# snow_depth_gauge_2A.net
KiCad netlist of a schematic drawn in EAGLE
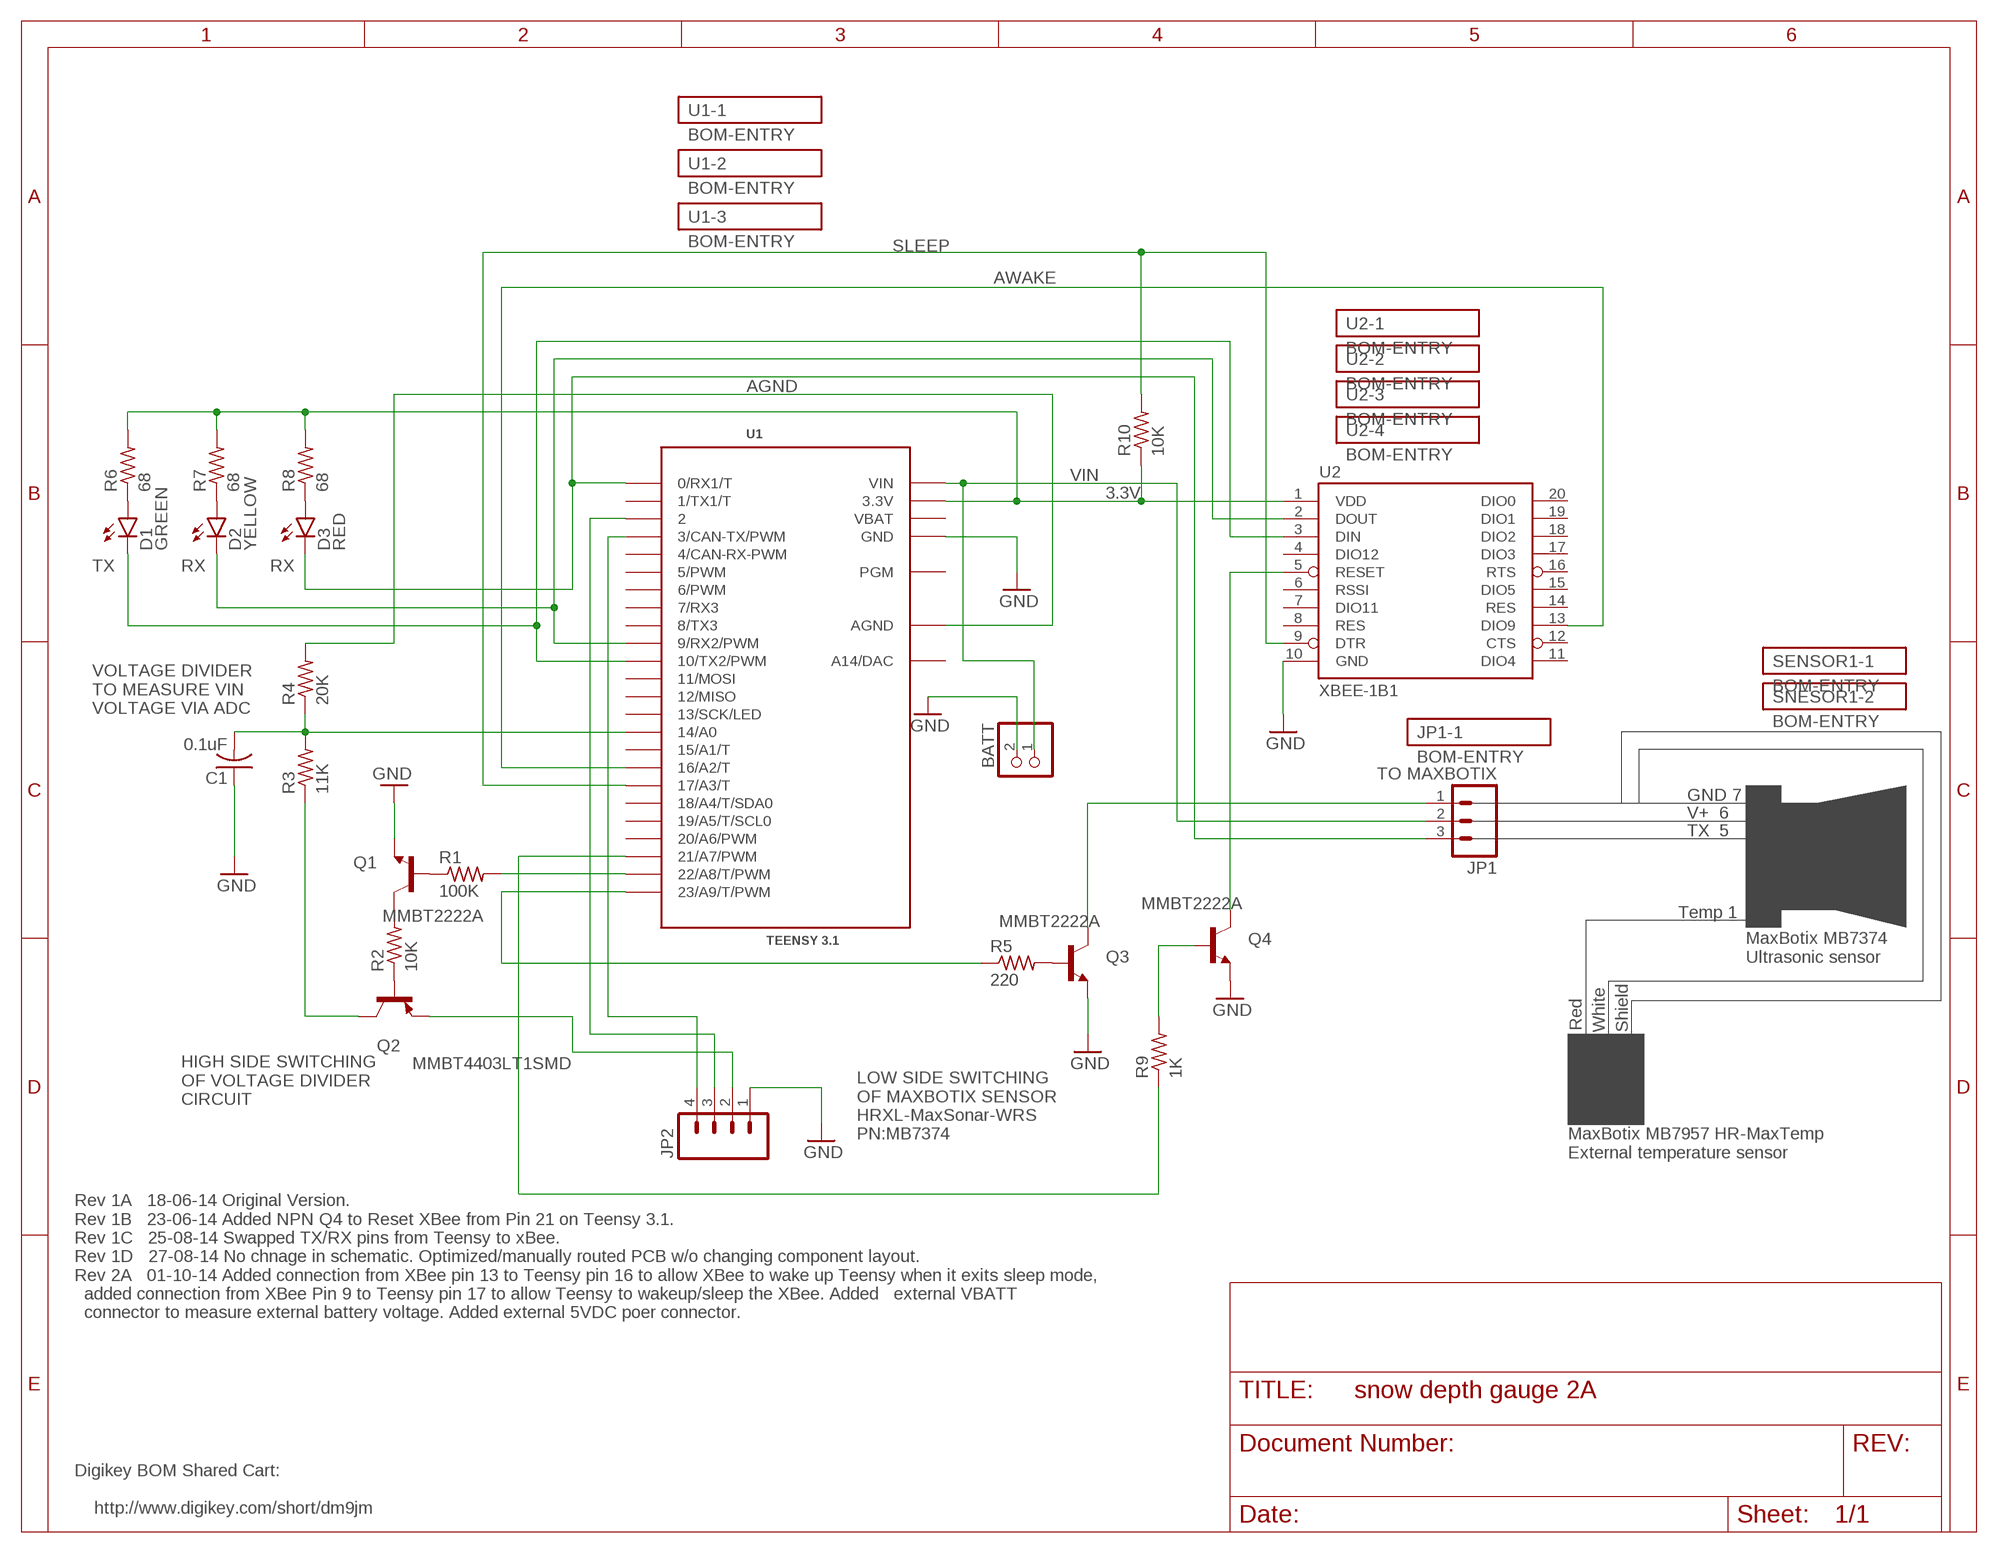
[diagram p0: schematic, sheet 1]

(export (version "E")
  (design (tool "Eeschema 10.0.6"))
  (components
    (comp (ref "BATT")
      (value "JST_2PIN-SMT-RA")
      (footprint "eagle-import:JST-PH-2-SMT-RA")
      (libsource (lib "eagle-import") (part "JST_2PIN-SMT-RA"))
    )
    (comp (ref "C1")
      (value "0.1uF")
      (footprint "eagle-import:C3216")
      (fields (field (name "PARTNO") "C1206C104K4RACTU"))
      (libsource (lib "eagle-import") (part "C-USC3216"))
    )
    (comp (ref "D1")
      (value "GREEN")
      (footprint "eagle-import:LED-0603")
      (fields (field (name "PARTNO") "LNJ337W83RA"))
      (libsource (lib "eagle-import") (part "LED-GREEN0603"))
    )
    (comp (ref "D2")
      (value "YELLOW")
      (footprint "eagle-import:LED-0603")
      (fields (field (name "PARTNO") "LNJ437W84RA"))
      (libsource (lib "eagle-import") (part "LED-YELLOW0603"))
    )
    (comp (ref "D3")
      (value "RED")
      (footprint "eagle-import:LED-0603")
      (fields (field (name "PARTNO") "LNJ237W82RA"))
      (libsource (lib "eagle-import") (part "LED-RED0603"))
    )
    (comp (ref "JP1")
      (value "TO MAXBOTIX")
      (footprint "eagle-import:MOLEX-1X3_LOCK")
      (fields (field (name "PARTNO") "0022292031"))
      (libsource (lib "eagle-import") (part "M03POLAR_LOCK"))
    )
    (comp (ref "JP2")
      (value "M04PTH")
      (footprint "eagle-import:1X04")
      (libsource (lib "eagle-import") (part "M04PTH"))
    )
    (comp (ref "Q1")
      (value "MMBT2222A")
      (footprint "eagle-import:SOT23-BEC")
      (libsource (lib "eagle-import") (part "-NPN-SOT23-BECMMBT2222ALT1"))
    )
    (comp (ref "Q2")
      (value "MMBT4403LT1SMD")
      (footprint "eagle-import:SOT23-BEC")
      (fields (field (name "PARTNO") "MMBT4403"))
      (libsource (lib "eagle-import") (part "MMBT4403SMDLT1"))
    )
    (comp (ref "Q3")
      (value "MMBT2222A")
      (footprint "eagle-import:SOT23-BEC")
      (libsource (lib "eagle-import") (part "-NPN-SOT23-BECMMBT2222ALT1"))
    )
    (comp (ref "Q4")
      (value "MMBT2222A")
      (footprint "eagle-import:SOT23-BEC")
      (libsource (lib "eagle-import") (part "-NPN-SOT23-BECMMBT2222ALT1"))
    )
    (comp (ref "R1")
      (value "100K")
      (footprint "eagle-import:R3216")
      (fields (field (name "PARTNO") "KTR18EZPJ104"))
      (libsource (lib "eagle-import") (part "R-US_R3216"))
    )
    (comp (ref "R2")
      (value "10K")
      (footprint "eagle-import:R3216")
      (fields (field (name "PARTNO") "KTR18EZPJ103"))
      (libsource (lib "eagle-import") (part "R-US_R3216"))
    )
    (comp (ref "R3")
      (value "11K")
      (footprint "eagle-import:R3216")
      (fields (field (name "PARTNO") "KTR18EZPF1102"))
      (libsource (lib "eagle-import") (part "R-US_R3216"))
    )
    (comp (ref "R4")
      (value "20K")
      (footprint "eagle-import:R3216")
      (fields (field (name "PARTNO") "KTR18EZPF2002"))
      (libsource (lib "eagle-import") (part "R-US_R3216"))
    )
    (comp (ref "R5")
      (value "220")
      (footprint "eagle-import:R3216")
      (fields (field (name "PARTNO") "KTR18EZPJ221"))
      (libsource (lib "eagle-import") (part "R-US_R3216"))
    )
    (comp (ref "R6")
      (value "68")
      (footprint "eagle-import:R3216")
      (fields (field (name "PARTNO") "KTR18EZPJ680"))
      (libsource (lib "eagle-import") (part "R-US_R3216"))
    )
    (comp (ref "R7")
      (value "68")
      (footprint "eagle-import:R3216")
      (fields (field (name "PARTNO") "KTR18EZPJ680"))
      (libsource (lib "eagle-import") (part "R-US_R3216"))
    )
    (comp (ref "R8")
      (value "68")
      (footprint "eagle-import:R3216")
      (fields (field (name "PARTNO") "KTR18EZPJ680"))
      (libsource (lib "eagle-import") (part "R-US_R3216"))
    )
    (comp (ref "R9")
      (value "1K")
      (footprint "eagle-import:R3216")
      (fields (field (name "PARTNO") "KTR18EZPJ102"))
      (libsource (lib "eagle-import") (part "R-US_R3216"))
    )
    (comp (ref "R10")
      (value "10K")
      (footprint "eagle-import:R3216")
      (fields (field (name "PARTNO") "KTR18EZPJ103"))
      (libsource (lib "eagle-import") (part "R-US_R3216"))
    )
    (comp (ref "U1")
      (value "TEENSY 3.1")
      (footprint "eagle-import:TEENSY_3.1_BASIC")
      (fields (field (name "PARTNO") "TEENSY31"))
      (libsource (lib "eagle-import") (part "TEENSY_3.1_BASIC"))
    )
    (comp (ref "U2")
      (value "XBEE-1B1")
      (footprint "eagle-import:XBEE-1")
      (fields (field (name "PARTNO") "XB24-AUI-001"))
      (libsource (lib "eagle-import") (part "XBEE-1B1"))
    )
  )
  (nets
    (net (code "1") (name "/3.3V") (class "Default")
      (node (ref "R10") (pin "1") (pinfunction "1_1") (pintype "passive"))
      (node (ref "R6") (pin "2") (pinfunction "2_2") (pintype "passive"))
      (node (ref "R7") (pin "2") (pinfunction "2_2") (pintype "passive"))
      (node (ref "R8") (pin "2") (pinfunction "2_2") (pintype "passive"))
      (node (ref "U1") (pin "3.3V") (pinfunction "3.3V_3.3V") (pintype "power_in"))
      (node (ref "U1") (pin "3.3V1") (pinfunction "3.3V_3.3V1") (pintype "power_in"))
      (node (ref "U2") (pin "1") (pinfunction "VDD_1") (pintype "power_in"))
    )
    (net (code "2") (name "/AGND") (class "Default")
      (node (ref "R4") (pin "2") (pinfunction "2_2") (pintype "passive"))
      (node (ref "U1") (pin "AGND") (pinfunction "AGND_AGND") (pintype "power_in"))
    )
    (net (code "3") (name "/AWAKE") (class "Default")
      (node (ref "U1") (pin "16/A2") (pinfunction "16/A2/T_16/A2") (pintype "bidirectional"))
      (node (ref "U2") (pin "13") (pinfunction "DIO9_13") (pintype "bidirectional"))
    )
    (net (code "4") (name "/SLEEP") (class "Default")
      (node (ref "R10") (pin "2") (pinfunction "2_2") (pintype "passive"))
      (node (ref "U1") (pin "17/A3") (pinfunction "17/A3/T_17/A3") (pintype "bidirectional"))
      (node (ref "U2") (pin "9") (pinfunction "DTR_9") (pintype "bidirectional"))
    )
    (net (code "5") (name "/VBAT") (class "Default")
      (node (ref "U1") (pin "VBAT") (pinfunction "VBAT_VBAT") (pintype "power_in"))
    )
    (net (code "6") (name "/VIN") (class "Default")
      (node (ref "BATT") (pin "1") (pinfunction "2_1") (pintype "passive"))
      (node (ref "JP1") (pin "2") (pinfunction "2_2") (pintype "passive"))
      (node (ref "U1") (pin "VIN") (pinfunction "VIN_VIN") (pintype "power_in"))
    )
    (net (code "7") (name "GND") (class "Default")
      (node (ref "BATT") (pin "2") (pinfunction "1_2") (pintype "passive"))
      (node (ref "C1") (pin "1") (pinfunction "1_1") (pintype "passive"))
      (node (ref "JP2") (pin "1") (pinfunction "1_1") (pintype "passive"))
      (node (ref "Q1") (pin "E") (pinfunction "E_E") (pintype "passive"))
      (node (ref "Q3") (pin "E") (pinfunction "E_E") (pintype "passive"))
      (node (ref "Q4") (pin "E") (pinfunction "E_E") (pintype "passive"))
      (node (ref "U1") (pin "GND") (pinfunction "GND_GND") (pintype "power_in"))
      (node (ref "U1") (pin "GND1") (pinfunction "GND_GND1") (pintype "power_in"))
      (node (ref "U2") (pin "10") (pinfunction "GND_10") (pintype "power_in"))
    )
    (net (code "8") (name "Net-(C1-Pad2)") (class "Default")
      (node (ref "C1") (pin "2") (pinfunction "2_2") (pintype "passive"))
      (node (ref "R3") (pin "2") (pinfunction "2_2") (pintype "passive"))
      (node (ref "R4") (pin "1") (pinfunction "1_1") (pintype "passive"))
      (node (ref "U1") (pin "14/A0") (pinfunction "14/A0_14/A0") (pintype "bidirectional"))
    )
    (net (code "9") (name "Net-(D1-PadA)") (class "Default")
      (node (ref "D1") (pin "A") (pinfunction "A_A") (pintype "passive"))
      (node (ref "R6") (pin "1") (pinfunction "1_1") (pintype "passive"))
    )
    (net (code "10") (name "Net-(D2-PadA)") (class "Default")
      (node (ref "D2") (pin "A") (pinfunction "A_A") (pintype "passive"))
      (node (ref "R7") (pin "1") (pinfunction "1_1") (pintype "passive"))
    )
    (net (code "11") (name "Net-(D3-PadA)") (class "Default")
      (node (ref "D3") (pin "A") (pinfunction "A_A") (pintype "passive"))
      (node (ref "R8") (pin "1") (pinfunction "1_1") (pintype "passive"))
    )
    (net (code "12") (name "Net-(JP1-Pad1)") (class "Default")
      (node (ref "JP1") (pin "1") (pinfunction "1_1") (pintype "passive"))
      (node (ref "Q3") (pin "C") (pinfunction "C_C") (pintype "passive"))
    )
    (net (code "13") (name "Net-(JP2-Pad2)") (class "Default")
      (node (ref "JP2") (pin "2") (pinfunction "2_2") (pintype "passive"))
      (node (ref "Q2") (pin "E") (pinfunction "E_E") (pintype "passive"))
    )
    (net (code "14") (name "Net-(JP2-Pad3)") (class "Default")
      (node (ref "JP2") (pin "3") (pinfunction "3_3") (pintype "passive"))
      (node (ref "U1") (pin "2") (pinfunction "2_2") (pintype "bidirectional"))
    )
    (net (code "15") (name "Net-(Q1-PadB)") (class "Default")
      (node (ref "Q1") (pin "B") (pinfunction "B_B") (pintype "passive"))
      (node (ref "R1") (pin "1") (pinfunction "1_1") (pintype "passive"))
    )
    (net (code "16") (name "Net-(Q1-PadC)") (class "Default")
      (node (ref "Q1") (pin "C") (pinfunction "C_C") (pintype "passive"))
      (node (ref "R2") (pin "2") (pinfunction "2_2") (pintype "passive"))
    )
    (net (code "17") (name "Net-(Q2-PadB)") (class "Default")
      (node (ref "Q2") (pin "B") (pinfunction "B_B") (pintype "passive"))
      (node (ref "R2") (pin "1") (pinfunction "1_1") (pintype "passive"))
    )
    (net (code "18") (name "Net-(Q2-PadC)") (class "Default")
      (node (ref "Q2") (pin "C") (pinfunction "C_C") (pintype "passive"))
      (node (ref "R3") (pin "1") (pinfunction "1_1") (pintype "passive"))
    )
    (net (code "19") (name "Net-(Q3-PadB)") (class "Default")
      (node (ref "Q3") (pin "B") (pinfunction "B_B") (pintype "passive"))
      (node (ref "R5") (pin "2") (pinfunction "2_2") (pintype "passive"))
    )
    (net (code "20") (name "Net-(Q4-PadB)") (class "Default")
      (node (ref "Q4") (pin "B") (pinfunction "B_B") (pintype "passive"))
      (node (ref "R9") (pin "2") (pinfunction "2_2") (pintype "passive"))
    )
    (net (code "21") (name "Net-(U1-0{slash}RX1{slash}T)") (class "Default")
      (node (ref "D3") (pin "C") (pinfunction "C_C") (pintype "passive"))
      (node (ref "JP1") (pin "3") (pinfunction "3_3") (pintype "passive"))
      (node (ref "U1") (pin "0") (pinfunction "0/RX1/T_0") (pintype "bidirectional"))
    )
    (net (code "22") (name "Net-(U1-3{slash}CAN-TX{slash}PWM)") (class "Default")
      (node (ref "JP2") (pin "4") (pinfunction "4_4") (pintype "passive"))
      (node (ref "U1") (pin "3") (pinfunction "3/CAN-TX/PWM_3") (pintype "bidirectional"))
    )
    (net (code "23") (name "Net-(U1-9{slash}RX2{slash}PWM)") (class "Default")
      (node (ref "D2") (pin "C") (pinfunction "C_C") (pintype "passive"))
      (node (ref "U1") (pin "9") (pinfunction "9/RX2/PWM_9") (pintype "bidirectional"))
      (node (ref "U2") (pin "2") (pinfunction "DOUT_2") (pintype "output"))
    )
    (net (code "24") (name "Net-(U1-10{slash}TX2{slash}PWM)") (class "Default")
      (node (ref "D1") (pin "C") (pinfunction "C_C") (pintype "passive"))
      (node (ref "U1") (pin "10") (pinfunction "10/TX2/PWM_10") (pintype "bidirectional"))
      (node (ref "U2") (pin "3") (pinfunction "DIN_3") (pintype "input"))
    )
    (net (code "25") (name "Net-(U1-21{slash}A7{slash}PWM)") (class "Default")
      (node (ref "R9") (pin "1") (pinfunction "1_1") (pintype "passive"))
      (node (ref "U1") (pin "21/A7") (pinfunction "21/A7/PWM_21/A7") (pintype "bidirectional"))
    )
    (net (code "26") (name "Net-(U1-22{slash}A8{slash}T{slash}PWM)") (class "Default")
      (node (ref "R1") (pin "2") (pinfunction "2_2") (pintype "passive"))
      (node (ref "U1") (pin "22/A8") (pinfunction "22/A8/T/PWM_22/A8") (pintype "bidirectional"))
    )
    (net (code "27") (name "Net-(U1-23{slash}A9{slash}T{slash}PWM)") (class "Default")
      (node (ref "R5") (pin "1") (pinfunction "1_1") (pintype "passive"))
      (node (ref "U1") (pin "23/A9") (pinfunction "23/A9/T/PWM_23/A9") (pintype "bidirectional"))
    )
    (net (code "28") (name "Net-(U2-RESET)") (class "Default")
      (node (ref "Q4") (pin "C") (pinfunction "C_C") (pintype "passive"))
      (node (ref "U2") (pin "5") (pinfunction "RESET_5") (pintype "input"))
    )
    (net (code "29") (name "unconnected-(U1-1{slash}TX1{slash}T-Pad1)") (class "Default")
      (node (ref "U1") (pin "1") (pinfunction "1/TX1/T_1") (pintype "bidirectional"))
    )
    (net (code "30") (name "unconnected-(U1-4{slash}CAN-RX-PWM-Pad4)") (class "Default")
      (node (ref "U1") (pin "4") (pinfunction "4/CAN-RX-PWM_4") (pintype "bidirectional"))
    )
    (net (code "31") (name "unconnected-(U1-5{slash}PWM-Pad5)") (class "Default")
      (node (ref "U1") (pin "5") (pinfunction "5/PWM_5") (pintype "bidirectional"))
    )
    (net (code "32") (name "unconnected-(U1-6{slash}PWM-Pad6)") (class "Default")
      (node (ref "U1") (pin "6") (pinfunction "6/PWM_6") (pintype "bidirectional"))
    )
    (net (code "33") (name "unconnected-(U1-7{slash}RX3-Pad7)") (class "Default")
      (node (ref "U1") (pin "7") (pinfunction "7/RX3_7") (pintype "bidirectional"))
    )
    (net (code "34") (name "unconnected-(U1-8{slash}TX3-Pad8)") (class "Default")
      (node (ref "U1") (pin "8") (pinfunction "8/TX3_8") (pintype "bidirectional"))
    )
    (net (code "35") (name "unconnected-(U1-11{slash}MOSI-Pad11)") (class "Default")
      (node (ref "U1") (pin "11") (pinfunction "11/MOSI_11") (pintype "bidirectional"))
    )
    (net (code "36") (name "unconnected-(U1-12{slash}MISO-Pad12)") (class "Default")
      (node (ref "U1") (pin "12") (pinfunction "12/MISO_12") (pintype "bidirectional"))
    )
    (net (code "37") (name "unconnected-(U1-13{slash}SCK{slash}LED-Pad13)") (class "Default")
      (node (ref "U1") (pin "13") (pinfunction "13/SCK/LED_13") (pintype "bidirectional"))
    )
    (net (code "38") (name "unconnected-(U1-15{slash}A1{slash}T-Pad15{slash}A1)") (class "Default")
      (node (ref "U1") (pin "15/A1") (pinfunction "15/A1/T_15/A1") (pintype "bidirectional"))
    )
    (net (code "39") (name "unconnected-(U1-18{slash}A4{slash}T{slash}SDA0-Pad18{slash}A4)") (class "Default")
      (node (ref "U1") (pin "18/A4") (pinfunction "18/A4/T/SDA0_18/A4") (pintype "bidirectional"))
    )
    (net (code "40") (name "unconnected-(U1-19{slash}A5{slash}T{slash}SCL0-Pad19{slash}A5)") (class "Default")
      (node (ref "U1") (pin "19/A5") (pinfunction "19/A5/T/SCL0_19/A5") (pintype "bidirectional"))
    )
    (net (code "41") (name "unconnected-(U1-20{slash}A6{slash}PWM-Pad20{slash}A6)") (class "Default")
      (node (ref "U1") (pin "20/A6") (pinfunction "20/A6/PWM_20/A6") (pintype "bidirectional"))
    )
    (net (code "42") (name "unconnected-(U1-A14{slash}DAC-PadA14)") (class "Default")
      (node (ref "U1") (pin "A14") (pinfunction "A14/DAC_A14") (pintype "bidirectional"))
    )
    (net (code "43") (name "unconnected-(U1-PadPGM)") (class "Default")
      (node (ref "U1") (pin "PGM") (pinfunction "PGM_PGM") (pintype "bidirectional"))
    )
    (net (code "44") (name "unconnected-(U2-CTS-Pad12)") (class "Default")
      (node (ref "U2") (pin "12") (pinfunction "CTS_12") (pintype "output"))
    )
    (net (code "45") (name "unconnected-(U2-DIO0-Pad20)") (class "Default")
      (node (ref "U2") (pin "20") (pinfunction "DIO0_20") (pintype "bidirectional"))
    )
    (net (code "46") (name "unconnected-(U2-DIO1-Pad19)") (class "Default")
      (node (ref "U2") (pin "19") (pinfunction "DIO1_19") (pintype "bidirectional"))
    )
    (net (code "47") (name "unconnected-(U2-DIO2-Pad18)") (class "Default")
      (node (ref "U2") (pin "18") (pinfunction "DIO2_18") (pintype "bidirectional"))
    )
    (net (code "48") (name "unconnected-(U2-DIO3-Pad17)") (class "Default")
      (node (ref "U2") (pin "17") (pinfunction "DIO3_17") (pintype "bidirectional"))
    )
    (net (code "49") (name "unconnected-(U2-DIO4-Pad11)") (class "Default")
      (node (ref "U2") (pin "11") (pinfunction "DIO4_11") (pintype "bidirectional"))
    )
    (net (code "50") (name "unconnected-(U2-DIO5-Pad15)") (class "Default")
      (node (ref "U2") (pin "15") (pinfunction "DIO5_15") (pintype "bidirectional"))
    )
    (net (code "51") (name "unconnected-(U2-DIO11-Pad7)") (class "Default")
      (node (ref "U2") (pin "7") (pinfunction "DIO11_7") (pintype "bidirectional"))
    )
    (net (code "52") (name "unconnected-(U2-DIO12-Pad4)") (class "Default")
      (node (ref "U2") (pin "4") (pinfunction "DIO12_4") (pintype "bidirectional"))
    )
    (net (code "53") (name "unconnected-(U2-RES-Pad8)") (class "Default")
      (node (ref "U2") (pin "8") (pinfunction "RES_8") (pintype "bidirectional"))
    )
    (net (code "54") (name "unconnected-(U2-RES-Pad14)") (class "Default")
      (node (ref "U2") (pin "14") (pinfunction "RES_14") (pintype "bidirectional"))
    )
    (net (code "55") (name "unconnected-(U2-RSSI-Pad6)") (class "Default")
      (node (ref "U2") (pin "6") (pinfunction "RSSI_6") (pintype "bidirectional"))
    )
    (net (code "56") (name "unconnected-(U2-RTS-Pad16)") (class "Default")
      (node (ref "U2") (pin "16") (pinfunction "RTS_16") (pintype "input"))
    )
  )
)
